# DigiPot_breakout_old.net
KiCad netlist of a schematic drawn in EAGLE
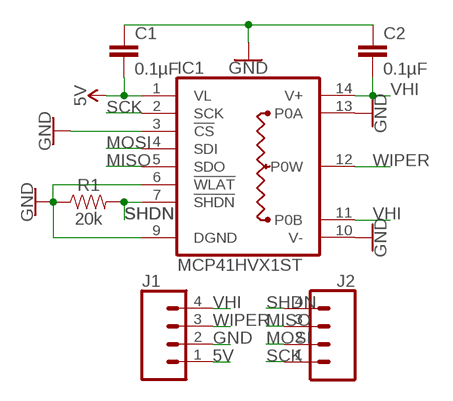
[diagram p0: schematic, sheet 1]

(export (version "E")
  (design (tool "Eeschema 10.0.6"))
  (components
    (comp (ref "C1")
      (value "0.1µF")
      (footprint "eagle-import:CAP-0.1I")
      (libsource (lib "eagle-import") (part "0.1µF-0.1''"))
    )
    (comp (ref "C2")
      (value "0.1µF")
      (footprint "eagle-import:CAP-0.1I")
      (libsource (lib "eagle-import") (part "0.1µF-0.1''"))
    )
    (comp (ref "IC1")
      (value "MCP41HVX1ST")
      (footprint "eagle-import:TSSOP14")
      (libsource (lib "eagle-import") (part "MCP41HVX1ST"))
    )
    (comp (ref "J1")
      (value "CONN_04")
      (footprint "eagle-import:1X04")
      (libsource (lib "eagle-import") (part "CONN_04"))
    )
    (comp (ref "J2")
      (value "CONN_04")
      (footprint "eagle-import:1X04")
      (libsource (lib "eagle-import") (part "CONN_04"))
    )
    (comp (ref "R1")
      (value "20k")
      (footprint "eagle-import:AXIAL-0.3")
      (libsource (lib "eagle-import") (part "1KOHM-HORIZ-1/4W-5%"))
    )
  )
  (nets
    (net (code "1") (name "/MISO") (class "Default")
      (node (ref "IC1") (pin "5") (pinfunction "SDO_5") (pintype "bidirectional"))
      (node (ref "J2") (pin "3") (pinfunction "3_3") (pintype "passive"))
    )
    (net (code "2") (name "/MOSI") (class "Default")
      (node (ref "IC1") (pin "4") (pinfunction "SDI_4") (pintype "bidirectional"))
      (node (ref "J2") (pin "2") (pinfunction "2_2") (pintype "passive"))
    )
    (net (code "3") (name "/SCK") (class "Default")
      (node (ref "IC1") (pin "2") (pinfunction "SCK_2") (pintype "bidirectional"))
      (node (ref "J2") (pin "1") (pinfunction "1_1") (pintype "passive"))
    )
    (net (code "4") (name "/SHDN") (class "Default")
      (node (ref "IC1") (pin "7") (pinfunction "~{SHDN}_7") (pintype "bidirectional"))
      (node (ref "J2") (pin "4") (pinfunction "4_4") (pintype "passive"))
      (node (ref "R1") (pin "P$2") (pinfunction "2_P$2") (pintype "passive"))
    )
    (net (code "5") (name "/VHI") (class "Default")
      (node (ref "C2") (pin "2") (pinfunction "2_2") (pintype "passive"))
      (node (ref "IC1") (pin "11") (pinfunction "P0B_11") (pintype "passive"))
      (node (ref "IC1") (pin "14") (pinfunction "V+_14") (pintype "power_in"))
      (node (ref "J1") (pin "4") (pinfunction "4_4") (pintype "passive"))
    )
    (net (code "6") (name "/WIPER") (class "Default")
      (node (ref "IC1") (pin "12") (pinfunction "P0W_12") (pintype "passive"))
      (node (ref "J1") (pin "3") (pinfunction "3_3") (pintype "passive"))
    )
    (net (code "7") (name "5V") (class "Default")
      (node (ref "C1") (pin "2") (pinfunction "2_2") (pintype "passive"))
      (node (ref "IC1") (pin "1") (pinfunction "VL_1") (pintype "power_in"))
      (node (ref "J1") (pin "1") (pinfunction "1_1") (pintype "passive"))
    )
    (net (code "8") (name "GND") (class "Default")
      (node (ref "C1") (pin "1") (pinfunction "1_1") (pintype "passive"))
      (node (ref "C2") (pin "1") (pinfunction "1_1") (pintype "passive"))
      (node (ref "IC1") (pin "10") (pinfunction "V-_10") (pintype "power_in"))
      (node (ref "IC1") (pin "13") (pinfunction "P0A_13") (pintype "passive"))
      (node (ref "IC1") (pin "3") (pinfunction "~{CS}_3") (pintype "bidirectional"))
      (node (ref "IC1") (pin "6") (pinfunction "~{WLAT}_6") (pintype "bidirectional"))
      (node (ref "IC1") (pin "9") (pinfunction "DGND_9") (pintype "power_in"))
      (node (ref "J1") (pin "2") (pinfunction "2_2") (pintype "passive"))
      (node (ref "R1") (pin "P$1") (pinfunction "1_P$1") (pintype "passive"))
    )
  )
)
